# MCU_Board_2021-08-30.net
KiCad netlist of a schematic drawn in Altium Designer
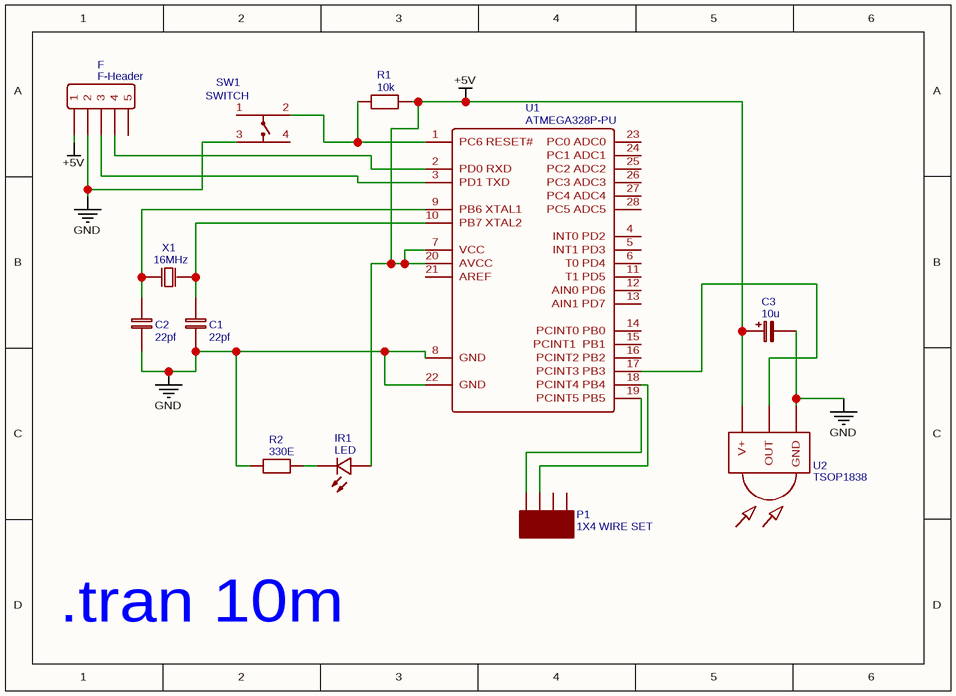
[diagram p0: MCU_Board_2021-08-30.schdoc]

(export (version "E")
  (design (tool "Eeschema 10.0.6"))
  (components
    (comp (ref "C1")
      (value "22pf")
      (fields (field (name "CONTRIBUTOR") "LCEDA_Lib"))
      (libsource (lib "altium-import") (part "root_3_22pf_"))
    )
    (comp (ref "C2")
      (value "22pf")
      (fields (field (name "CONTRIBUTOR") "LCEDA_Lib"))
      (libsource (lib "altium-import") (part "root_3_22pf_"))
    )
    (comp (ref "C3")
      (value "10u")
      (fields (field (name "CONTRIBUTOR") "LCEDA_Lib"))
      (libsource (lib "altium-import") (part "root_0_10u_"))
    )
    (comp (ref "F")
      (value "F-Header")
      (fields (field (name "CONTRIBUTOR") "dfemery"))
      (libsource (lib "altium-import") (part "root_1_F-Header_"))
    )
    (comp (ref "IR1")
      (value "LED")
      (fields
        (field (name "BOM_MANUFACTURER PART") "IR333C/H0/L10")
        (field (name "BOM_SUPPLIER PART") "C72053")
      )
      (libsource (lib "altium-import") (part "root_2_LED_"))
    )
    (comp (ref "P1")
      (value "1X4 WIRE SET")
      (fields
        (field (name "BOM_SUPPLIER PART") "C44527")
        (field (name "BOM_MANUFACTURER PART") "Header-Female-2.54_1x4")
      )
      (libsource (lib "altium-import") (part "root_3_1X4 WIRE SET_"))
    )
    (comp (ref "R1")
      (value "10k")
      (fields (field (name "CONTRIBUTOR") "LCEDA_Lib"))
      (libsource (lib "altium-import") (part "root_0_10k_"))
    )
    (comp (ref "R2")
      (value "330E")
      (fields (field (name "CONTRIBUTOR") "LCEDA_Lib"))
      (libsource (lib "altium-import") (part "root_2_330E_"))
    )
    (comp (ref "SW1")
      (value "SWITCH")
      (fields (field (name "CONTRIBUTOR") "Moile-EasyEDA"))
      (libsource (lib "altium-import") (part "root_0_SWITCH_"))
    )
    (comp (ref "U1")
      (value "ATMEGA328P-PU")
      (fields (field (name "BOM_SUPPLIER PART") "C33901") (field (name "CONTRIBUTOR") "LCSC"))
      (libsource (lib "altium-import") (part "root_0_ATMEGA328P-PU_"))
    )
    (comp (ref "U2") (value "TSOP1838") (libsource (lib "altium-import") (part "root_1_TSOP1838_")))
    (comp (ref "X1")
      (value "16MHz")
      (fields
        (field (name "BOM_MANUFACTURER PART") "E49A16E00000KE10CO")
        (field (name "BOM_SUPPLIER PART") "C114981")
      )
      (libsource (lib "altium-import") (part "root_0_16MHz_"))
    )
  )
  (nets
    (net (code "1") (name "+5V") (class "Default")
      (node (ref "C3") (pin "1") (pinfunction "1_1") (pintype "passive"))
      (node (ref "F") (pin "1") (pinfunction "1_1") (pintype "passive"))
      (node (ref "IR1") (pin "1") (pinfunction "A_1") (pintype "passive"))
      (node (ref "R1") (pin "2") (pinfunction "2_2") (pintype "passive"))
      (node (ref "U1") (pin "20") (pinfunction "AVCC_20") (pintype "passive"))
      (node (ref "U1") (pin "7") (pinfunction "VCC_7") (pintype "passive"))
      (node (ref "U2") (pin "VCC") (pinfunction "V+_VCC") (pintype "passive"))
    )
    (net (code "2") (name "GND") (class "Default")
      (node (ref "C1") (pin "2") (pinfunction "2_2") (pintype "passive"))
      (node (ref "C2") (pin "2") (pinfunction "2_2") (pintype "passive"))
      (node (ref "C3") (pin "2") (pinfunction "2_2") (pintype "passive"))
      (node (ref "F") (pin "2") (pinfunction "2_2") (pintype "passive"))
      (node (ref "R2") (pin "2") (pinfunction "2_2") (pintype "passive"))
      (node (ref "SW1") (pin "3") (pinfunction "3_3") (pintype "passive"))
      (node (ref "U1") (pin "22") (pinfunction "GND_22") (pintype "passive"))
      (node (ref "U1") (pin "8") (pinfunction "GND_8") (pintype "passive"))
      (node (ref "U2") (pin "GND") (pinfunction "GND_GND") (pintype "passive"))
    )
    (net (code "3") (name "Net-(IR1-C)") (class "Default")
      (node (ref "IR1") (pin "2") (pinfunction "C_2") (pintype "passive"))
      (node (ref "R2") (pin "1") (pinfunction "1_1") (pintype "passive"))
    )
    (net (code "4") (name "Net-(P1-3)") (class "Default")
      (node (ref "P1") (pin "4") (pinfunction "3_4") (pintype "passive"))
      (node (ref "U1") (pin "18") (pinfunction "PCINT4_PB4_18") (pintype "passive"))
    )
    (net (code "5") (name "Net-(P1-4)") (class "Default")
      (node (ref "P1") (pin "3") (pinfunction "4_3") (pintype "passive"))
      (node (ref "U1") (pin "19") (pinfunction "PCINT5_PB5_19") (pintype "passive"))
    )
    (net (code "6") (name "Net-(U1-PB6_XTAL1)") (class "Default")
      (node (ref "C2") (pin "1") (pinfunction "1_1") (pintype "passive"))
      (node (ref "U1") (pin "9") (pinfunction "PB6_XTAL1_9") (pintype "passive"))
      (node (ref "X1") (pin "1") (pinfunction "OSC1_1") (pintype "passive"))
    )
    (net (code "7") (name "Net-(U1-PB7_XTAL2)") (class "Default")
      (node (ref "C1") (pin "1") (pinfunction "1_1") (pintype "passive"))
      (node (ref "U1") (pin "10") (pinfunction "PB7_XTAL2_10") (pintype "passive"))
      (node (ref "X1") (pin "2") (pinfunction "OSC2_2") (pintype "passive"))
    )
    (net (code "8") (name "Net-(U1-PC6_RESET#)") (class "Default")
      (node (ref "R1") (pin "1") (pinfunction "1_1") (pintype "passive"))
      (node (ref "SW1") (pin "2") (pinfunction "2_2") (pintype "passive"))
      (node (ref "U1") (pin "1") (pinfunction "PC6_RESET#_1") (pintype "passive"))
    )
    (net (code "9") (name "Net-(U1-PCINT3_PB3)") (class "Default")
      (node (ref "U1") (pin "17") (pinfunction "PCINT3_PB3_17") (pintype "passive"))
      (node (ref "U2") (pin "OUT") (pinfunction "OUT_OUT") (pintype "passive"))
    )
    (net (code "10") (name "Net-(U1-PD0_RXD)") (class "Default")
      (node (ref "F") (pin "4") (pinfunction "4_4") (pintype "passive"))
      (node (ref "U1") (pin "2") (pinfunction "PD0_RXD_2") (pintype "passive"))
    )
    (net (code "11") (name "Net-(U1-PD1_TXD)") (class "Default")
      (node (ref "F") (pin "3") (pinfunction "3_3") (pintype "passive"))
      (node (ref "U1") (pin "3") (pinfunction "PD1_TXD_3") (pintype "passive"))
    )
    (net (code "12") (name "unconnected-(F-Pad5)") (class "Default")
      (node (ref "F") (pin "5") (pinfunction "5_5") (pintype "passive"))
    )
    (net (code "13") (name "unconnected-(P1-Pad1)") (class "Default")
      (node (ref "P1") (pin "1") (pinfunction "1_1") (pintype "passive"))
    )
    (net (code "14") (name "unconnected-(P1-Pad2)") (class "Default")
      (node (ref "P1") (pin "2") (pinfunction "2_2") (pintype "passive"))
    )
    (net (code "15") (name "unconnected-(SW1-Pad1)") (class "Default")
      (node (ref "SW1") (pin "1") (pinfunction "1_1") (pintype "passive"))
    )
    (net (code "16") (name "unconnected-(SW1-Pad4)") (class "Default")
      (node (ref "SW1") (pin "4") (pinfunction "4_4") (pintype "passive"))
    )
    (net (code "17") (name "unconnected-(U1-AIN0_PD6-Pad12)") (class "Default")
      (node (ref "U1") (pin "12") (pinfunction "AIN0_PD6_12") (pintype "passive"))
    )
    (net (code "18") (name "unconnected-(U1-AIN1_PD7-Pad13)") (class "Default")
      (node (ref "U1") (pin "13") (pinfunction "AIN1_PD7_13") (pintype "passive"))
    )
    (net (code "19") (name "unconnected-(U1-AREF-Pad21)") (class "Default")
      (node (ref "U1") (pin "21") (pinfunction "AREF_21") (pintype "passive"))
    )
    (net (code "20") (name "unconnected-(U1-INT0_PD2-Pad4)") (class "Default")
      (node (ref "U1") (pin "4") (pinfunction "INT0_PD2_4") (pintype "passive"))
    )
    (net (code "21") (name "unconnected-(U1-INT1_PD3-Pad5)") (class "Default")
      (node (ref "U1") (pin "5") (pinfunction "INT1_PD3_5") (pintype "passive"))
    )
    (net (code "22") (name "unconnected-(U1-PC0_ADC0-Pad23)") (class "Default")
      (node (ref "U1") (pin "23") (pinfunction "PC0_ADC0_23") (pintype "passive"))
    )
    (net (code "23") (name "unconnected-(U1-PC1_ADC1-Pad24)") (class "Default")
      (node (ref "U1") (pin "24") (pinfunction "PC1_ADC1_24") (pintype "passive"))
    )
    (net (code "24") (name "unconnected-(U1-PC2_ADC2-Pad25)") (class "Default")
      (node (ref "U1") (pin "25") (pinfunction "PC2_ADC2_25") (pintype "passive"))
    )
    (net (code "25") (name "unconnected-(U1-PC3_ADC3-Pad26)") (class "Default")
      (node (ref "U1") (pin "26") (pinfunction "PC3_ADC3_26") (pintype "passive"))
    )
    (net (code "26") (name "unconnected-(U1-PC4_ADC4-Pad27)") (class "Default")
      (node (ref "U1") (pin "27") (pinfunction "PC4_ADC4_27") (pintype "passive"))
    )
    (net (code "27") (name "unconnected-(U1-PC5_ADC5-Pad28)") (class "Default")
      (node (ref "U1") (pin "28") (pinfunction "PC5_ADC5_28") (pintype "passive"))
    )
    (net (code "28") (name "unconnected-(U1-PCINT0_PB0-Pad14)") (class "Default")
      (node (ref "U1") (pin "14") (pinfunction "PCINT0_PB0_14") (pintype "passive"))
    )
    (net (code "29") (name "unconnected-(U1-PCINT1__PB1-Pad15)") (class "Default")
      (node (ref "U1") (pin "15") (pinfunction "PCINT1__PB1_15") (pintype "passive"))
    )
    (net (code "30") (name "unconnected-(U1-PCINT2_PB2-Pad16)") (class "Default")
      (node (ref "U1") (pin "16") (pinfunction "PCINT2_PB2_16") (pintype "passive"))
    )
    (net (code "31") (name "unconnected-(U1-T0_PD4-Pad6)") (class "Default")
      (node (ref "U1") (pin "6") (pinfunction "T0_PD4_6") (pintype "passive"))
    )
    (net (code "32") (name "unconnected-(U1-T1_PD5-Pad11)") (class "Default")
      (node (ref "U1") (pin "11") (pinfunction "T1_PD5_11") (pintype "passive"))
    )
  )
)
